# SCH_AP-DIsplay-2_1_Altium.net
KiCad netlist of a schematic drawn in Altium Designer
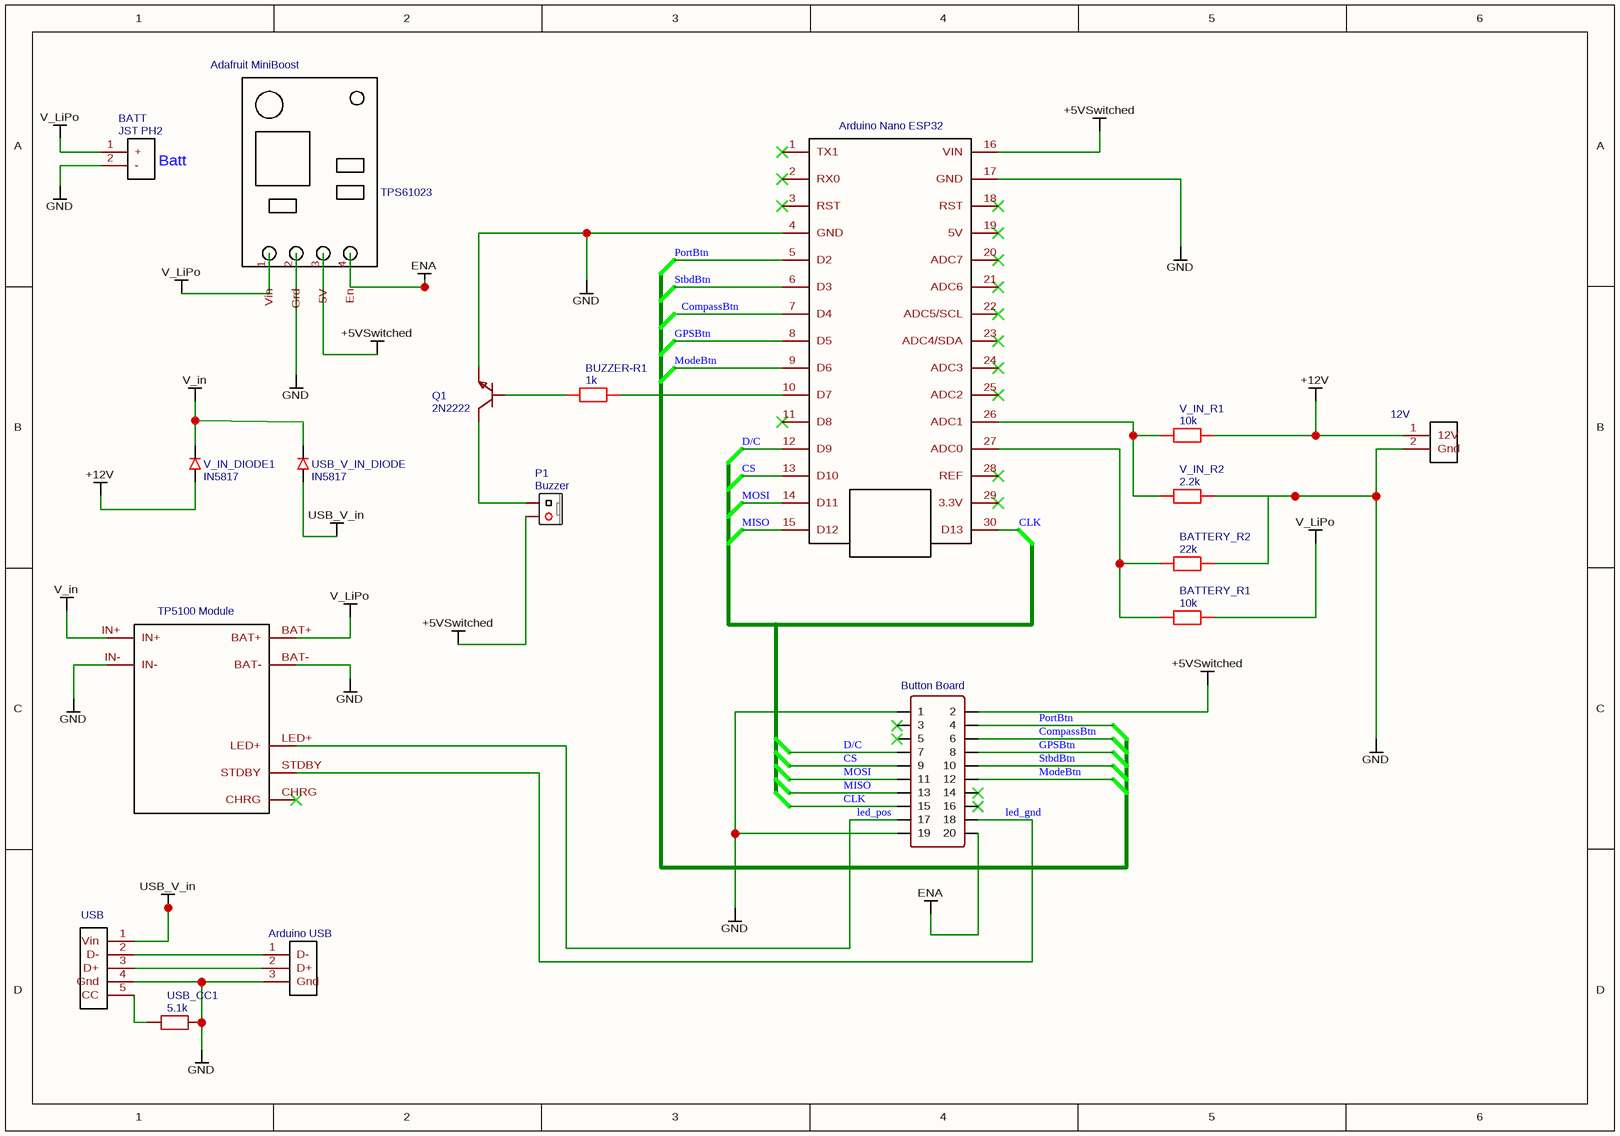
[diagram p0: SCH_AP-DIsplay-2.1_Altium.schdoc]

(export (version "E")
  (design (tool "Eeschema 10.0.6"))
  (components
    (comp (ref "1X2_JST_XH")
      (value "12V")
      (fields (field (name "CONTRIBUTOR") "edelarosar1700"))
      (libsource (lib "altium-import") (part "root_2_12V_"))
    )
    (comp (ref "BATT")
      (value "JST PH2")
      (fields (field (name "CONTRIBUTOR") "pwarrow99"))
      (libsource (lib "altium-import") (part "root_0_JST PH2_"))
    )
    (comp (ref "BATTERY_R1")
      (value "10k")
      (fields (field (name "CONTRIBUTOR") "Kagutsuchi"))
      (libsource (lib "altium-import") (part "root_0_10k_"))
    )
    (comp (ref "BATTERY_R2")
      (value "22k")
      (fields (field (name "CONTRIBUTOR") "Kagutsuchi"))
      (libsource (lib "altium-import") (part "root_0_22k_"))
    )
    (comp (ref "BUTTON_LED1")
      (value "Button Board")
      (fields (field (name "CONTRIBUTOR") "LCEDA_Lib"))
      (libsource (lib "altium-import") (part "root_0_Button Board_"))
    )
    (comp (ref "BUZZER-R1")
      (value "1k")
      (fields (field (name "CONTRIBUTOR") "Kagutsuchi"))
      (libsource (lib "altium-import") (part "root_0_1k_"))
    )
    (comp (ref "JST_XH_1X3")
      (value "Arduino USB")
      (fields (field (name "CONTRIBUTOR") "GeMeMe"))
      (libsource (lib "altium-import") (part "root_0_Arduino USB_"))
    )
    (comp (ref "JST_XH_1X5")
      (value "USB")
      (fields (field (name "CONTRIBUTOR") "GeMeMe"))
      (libsource (lib "altium-import") (part "root_0_USB_"))
    )
    (comp (ref "P1")
      (value "Buzzer")
      (fields
        (field (name "MANUFACTURER PART") "Headers  Pins2.54mm1*10P")
        (field (name "CONTRIBUTOR") "jousterde1")
      )
      (libsource (lib "altium-import") (part "root_0_Buzzer_"))
    )
    (comp (ref "Q1")
      (value "2N2222")
      (fields
        (field (name "MANUFACTURER") "ST(先科)")
        (field (name "MANUFACTURER PART") "2N2222A")
        (field (name "CONTRIBUTOR") "LCSC")
      )
      (libsource (lib "altium-import") (part "root_2_2N2222_"))
    )
    (comp (ref "TPS61023")
      (value "Adafruit MiniBoost")
      (fields (field (name "CONTRIBUTOR") "jefflorditch"))
      (libsource (lib "altium-import") (part "root_0_Adafruit MiniBoost_"))
    )
    (comp (ref "U1")
      (value "Arduino Nano ESP32")
      (fields (field (name "CONTRIBUTOR") "Nikolay Yanev"))
      (libsource (lib "altium-import") (part "root_0_Arduino Nano ESP32_"))
    )
    (comp (ref "U3")
      (value "TP5100 Module")
      (fields (field (name "MANUFACTURER PART") "TP5100-MODULE") (field (name "CONTRIBUTOR") "cropemail"))
      (libsource (lib "altium-import") (part "root_0_TP5100 Module_"))
    )
    (comp (ref "USB_CC1")
      (value "5.1k")
      (fields (field (name "CONTRIBUTOR") "LCEDA_Lib"))
      (libsource (lib "altium-import") (part "root_2_5.1k_"))
    )
    (comp (ref "USB_V_IN_DIODE")
      (value "IN5817")
      (fields (field (name "MANUFACTURER PART") "DIODE") (field (name "CONTRIBUTOR") "mimit.oscar"))
      (libsource (lib "altium-import") (part "root_1_IN5817_"))
    )
    (comp (ref "V_IN_DIODE1")
      (value "IN5817")
      (fields (field (name "MANUFACTURER PART") "DIODE") (field (name "CONTRIBUTOR") "mimit.oscar"))
      (libsource (lib "altium-import") (part "root_1_IN5817_"))
    )
    (comp (ref "V_IN_R1")
      (value "10k")
      (fields (field (name "CONTRIBUTOR") "Kagutsuchi"))
      (libsource (lib "altium-import") (part "root_0_10k_"))
    )
    (comp (ref "V_IN_R2")
      (value "2.2k")
      (fields (field (name "CONTRIBUTOR") "Kagutsuchi"))
      (libsource (lib "altium-import") (part "root_0_2.2k_"))
    )
  )
  (nets
    (net (code "1") (name "+5VSwitched") (class "Default")
      (node (ref "BUTTON_LED1") (pin "2") (pinfunction "2_2") (pintype "passive"))
      (node (ref "P1") (pin "2") (pinfunction "2_2") (pintype "passive"))
      (node (ref "TPS61023") (pin "3") (pinfunction "5V_3") (pintype "passive"))
      (node (ref "U1") (pin "16") (pinfunction "VIN_16") (pintype "passive"))
    )
    (net (code "2") (name "+12V") (class "Default")
      (node (ref "1X2_JST_XH") (pin "1") (pinfunction "12V_1") (pintype "passive"))
      (node (ref "V_IN_DIODE1") (pin "1") (pinfunction "1_1") (pintype "passive"))
      (node (ref "V_IN_R1") (pin "2") (pinfunction "1_2") (pintype "passive"))
    )
    (net (code "3") (name "/CLK") (class "Default")
      (node (ref "BUTTON_LED1") (pin "15") (pinfunction "15_15") (pintype "passive"))
      (node (ref "U1") (pin "30") (pinfunction "D13_30") (pintype "passive"))
    )
    (net (code "4") (name "/CS") (class "Default")
      (node (ref "BUTTON_LED1") (pin "9") (pinfunction "9_9") (pintype "passive"))
      (node (ref "U1") (pin "13") (pinfunction "D10_13") (pintype "passive"))
    )
    (net (code "5") (name "/CompassBtn") (class "Default")
      (node (ref "BUTTON_LED1") (pin "6") (pinfunction "6_6") (pintype "passive"))
      (node (ref "U1") (pin "7") (pinfunction "D4_7") (pintype "passive"))
    )
    (net (code "6") (name "/D{slash}C") (class "Default")
      (node (ref "BUTTON_LED1") (pin "7") (pinfunction "7_7") (pintype "passive"))
      (node (ref "U1") (pin "12") (pinfunction "D9_12") (pintype "passive"))
    )
    (net (code "7") (name "/GPSBtn") (class "Default")
      (node (ref "BUTTON_LED1") (pin "8") (pinfunction "8_8") (pintype "passive"))
      (node (ref "U1") (pin "8") (pinfunction "D5_8") (pintype "passive"))
    )
    (net (code "8") (name "/MISO") (class "Default")
      (node (ref "BUTTON_LED1") (pin "13") (pinfunction "13_13") (pintype "passive"))
      (node (ref "U1") (pin "15") (pinfunction "D12_15") (pintype "passive"))
    )
    (net (code "9") (name "/MOSI") (class "Default")
      (node (ref "BUTTON_LED1") (pin "11") (pinfunction "11_11") (pintype "passive"))
      (node (ref "U1") (pin "14") (pinfunction "D11_14") (pintype "passive"))
    )
    (net (code "10") (name "/ModeBtn") (class "Default")
      (node (ref "BUTTON_LED1") (pin "12") (pinfunction "12_12") (pintype "passive"))
      (node (ref "U1") (pin "9") (pinfunction "D6_9") (pintype "passive"))
    )
    (net (code "11") (name "/PortBtn") (class "Default")
      (node (ref "BUTTON_LED1") (pin "4") (pinfunction "4_4") (pintype "passive"))
      (node (ref "U1") (pin "5") (pinfunction "D2_5") (pintype "passive"))
    )
    (net (code "12") (name "/StbdBtn") (class "Default")
      (node (ref "BUTTON_LED1") (pin "10") (pinfunction "10_10") (pintype "passive"))
      (node (ref "U1") (pin "6") (pinfunction "D3_6") (pintype "passive"))
    )
    (net (code "13") (name "/led_gnd") (class "Default")
      (node (ref "BUTTON_LED1") (pin "18") (pinfunction "18_18") (pintype "passive"))
      (node (ref "U3") (pin "STDBY") (pinfunction "STDBY_STDBY") (pintype "passive"))
    )
    (net (code "14") (name "/led_pos") (class "Default")
      (node (ref "BUTTON_LED1") (pin "17") (pinfunction "17_17") (pintype "passive"))
      (node (ref "U3") (pin "LED+") (pinfunction "LED+_LED+") (pintype "passive"))
    )
    (net (code "15") (name "ENA") (class "Default")
      (node (ref "BUTTON_LED1") (pin "20") (pinfunction "20_20") (pintype "passive"))
      (node (ref "TPS61023") (pin "4") (pinfunction "En_4") (pintype "passive"))
    )
    (net (code "16") (name "GND") (class "Default")
      (node (ref "1X2_JST_XH") (pin "2") (pinfunction "Gnd_2") (pintype "passive"))
      (node (ref "BATT") (pin "2") (pinfunction "-_2") (pintype "passive"))
      (node (ref "BATTERY_R2") (pin "2") (pinfunction "1_2") (pintype "passive"))
      (node (ref "BUTTON_LED1") (pin "1") (pinfunction "1_1") (pintype "passive"))
      (node (ref "BUTTON_LED1") (pin "19") (pinfunction "19_19") (pintype "passive"))
      (node (ref "JST_XH_1X3") (pin "3") (pinfunction "Gnd_3") (pintype "passive"))
      (node (ref "JST_XH_1X5") (pin "4") (pinfunction "Gnd_4") (pintype "passive"))
      (node (ref "Q1") (pin "1") (pinfunction "E_1") (pintype "passive"))
      (node (ref "TPS61023") (pin "2") (pinfunction "Grd_2") (pintype "passive"))
      (node (ref "U1") (pin "17") (pinfunction "GND_17") (pintype "passive"))
      (node (ref "U1") (pin "4") (pinfunction "GND_4") (pintype "passive"))
      (node (ref "U3") (pin "BAT-") (pinfunction "BAT-_BAT-") (pintype "passive"))
      (node (ref "U3") (pin "IN-") (pinfunction "IN-_IN-") (pintype "passive"))
      (node (ref "USB_CC1") (pin "1") (pinfunction "1_1") (pintype "passive"))
      (node (ref "V_IN_R2") (pin "2") (pinfunction "1_2") (pintype "passive"))
    )
    (net (code "17") (name "Net-(BATTERY_R1-2)") (class "Default")
      (node (ref "BATTERY_R1") (pin "1") (pinfunction "2_1") (pintype "passive"))
      (node (ref "BATTERY_R2") (pin "1") (pinfunction "2_1") (pintype "passive"))
      (node (ref "U1") (pin "27") (pinfunction "ADC0_27") (pintype "passive"))
    )
    (net (code "18") (name "Net-(BUZZER-R1-1)") (class "Default")
      (node (ref "BUZZER-R1") (pin "2") (pinfunction "1_2") (pintype "passive"))
      (node (ref "U1") (pin "10") (pinfunction "D7_10") (pintype "passive"))
    )
    (net (code "19") (name "Net-(BUZZER-R1-2)") (class "Default")
      (node (ref "BUZZER-R1") (pin "1") (pinfunction "2_1") (pintype "passive"))
      (node (ref "Q1") (pin "2") (pinfunction "B_2") (pintype "passive"))
    )
    (net (code "20") (name "Net-(JST_XH_1X3-D+)") (class "Default")
      (node (ref "JST_XH_1X3") (pin "2") (pinfunction "D+_2") (pintype "passive"))
      (node (ref "JST_XH_1X5") (pin "3") (pinfunction "D+_3") (pintype "passive"))
    )
    (net (code "21") (name "Net-(JST_XH_1X3-D-)") (class "Default")
      (node (ref "JST_XH_1X3") (pin "1") (pinfunction "D-_1") (pintype "passive"))
      (node (ref "JST_XH_1X5") (pin "2") (pinfunction "D-_2") (pintype "passive"))
    )
    (net (code "22") (name "Net-(JST_XH_1X5-CC)") (class "Default")
      (node (ref "JST_XH_1X5") (pin "5") (pinfunction "CC_5") (pintype "passive"))
      (node (ref "USB_CC1") (pin "2") (pinfunction "2_2") (pintype "passive"))
    )
    (net (code "23") (name "Net-(Q1-C)") (class "Default")
      (node (ref "P1") (pin "1") (pinfunction "1_1") (pintype "passive"))
      (node (ref "Q1") (pin "3") (pinfunction "C_3") (pintype "passive"))
    )
    (net (code "24") (name "Net-(U1-ADC1)") (class "Default")
      (node (ref "U1") (pin "26") (pinfunction "ADC1_26") (pintype "passive"))
      (node (ref "V_IN_R1") (pin "1") (pinfunction "2_1") (pintype "passive"))
      (node (ref "V_IN_R2") (pin "1") (pinfunction "2_1") (pintype "passive"))
    )
    (net (code "25") (name "USB_V_in") (class "Default")
      (node (ref "JST_XH_1X5") (pin "1") (pinfunction "Vin_1") (pintype "passive"))
      (node (ref "USB_V_IN_DIODE") (pin "1") (pinfunction "1_1") (pintype "passive"))
    )
    (net (code "26") (name "V_LiPo") (class "Default")
      (node (ref "BATT") (pin "1") (pinfunction "+_1") (pintype "passive"))
      (node (ref "BATTERY_R1") (pin "2") (pinfunction "1_2") (pintype "passive"))
      (node (ref "TPS61023") (pin "1") (pinfunction "Vin_1") (pintype "passive"))
      (node (ref "U3") (pin "BAT+") (pinfunction "BAT+_BAT+") (pintype "passive"))
    )
    (net (code "27") (name "V_in") (class "Default")
      (node (ref "U3") (pin "IN+") (pinfunction "IN+_IN+") (pintype "passive"))
      (node (ref "USB_V_IN_DIODE") (pin "2") (pinfunction "2_2") (pintype "passive"))
      (node (ref "V_IN_DIODE1") (pin "2") (pinfunction "2_2") (pintype "passive"))
    )
    (net (code "28") (name "unconnected-(BUTTON_LED1-Pad3)") (class "Default")
      (node (ref "BUTTON_LED1") (pin "3") (pinfunction "3_3") (pintype "passive+no_connect"))
    )
    (net (code "29") (name "unconnected-(BUTTON_LED1-Pad5)") (class "Default")
      (node (ref "BUTTON_LED1") (pin "5") (pinfunction "5_5") (pintype "passive+no_connect"))
    )
    (net (code "30") (name "unconnected-(BUTTON_LED1-Pad14)") (class "Default")
      (node (ref "BUTTON_LED1") (pin "14") (pinfunction "14_14") (pintype "passive+no_connect"))
    )
    (net (code "31") (name "unconnected-(BUTTON_LED1-Pad16)") (class "Default")
      (node (ref "BUTTON_LED1") (pin "16") (pinfunction "16_16") (pintype "passive+no_connect"))
    )
    (net (code "32") (name "unconnected-(U1-3.3V-Pad29)") (class "Default")
      (node (ref "U1") (pin "29") (pinfunction "3.3V_29") (pintype "passive+no_connect"))
    )
    (net (code "33") (name "unconnected-(U1-5V-Pad19)") (class "Default")
      (node (ref "U1") (pin "19") (pinfunction "5V_19") (pintype "passive+no_connect"))
    )
    (net (code "34") (name "unconnected-(U1-ADC2-Pad25)") (class "Default")
      (node (ref "U1") (pin "25") (pinfunction "ADC2_25") (pintype "passive+no_connect"))
    )
    (net (code "35") (name "unconnected-(U1-ADC3-Pad24)") (class "Default")
      (node (ref "U1") (pin "24") (pinfunction "ADC3_24") (pintype "passive+no_connect"))
    )
    (net (code "36") (name "unconnected-(U1-ADC4{slash}SDA-Pad23)") (class "Default")
      (node (ref "U1") (pin "23") (pinfunction "ADC4/SDA_23") (pintype "passive+no_connect"))
    )
    (net (code "37") (name "unconnected-(U1-ADC5{slash}SCL-Pad22)") (class "Default")
      (node (ref "U1") (pin "22") (pinfunction "ADC5/SCL_22") (pintype "passive+no_connect"))
    )
    (net (code "38") (name "unconnected-(U1-ADC6-Pad21)") (class "Default")
      (node (ref "U1") (pin "21") (pinfunction "ADC6_21") (pintype "passive+no_connect"))
    )
    (net (code "39") (name "unconnected-(U1-ADC7-Pad20)") (class "Default")
      (node (ref "U1") (pin "20") (pinfunction "ADC7_20") (pintype "passive+no_connect"))
    )
    (net (code "40") (name "unconnected-(U1-D8-Pad11)") (class "Default")
      (node (ref "U1") (pin "11") (pinfunction "D8_11") (pintype "passive+no_connect"))
    )
    (net (code "41") (name "unconnected-(U1-REF-Pad28)") (class "Default")
      (node (ref "U1") (pin "28") (pinfunction "REF_28") (pintype "passive+no_connect"))
    )
    (net (code "42") (name "unconnected-(U1-RST-Pad3)") (class "Default")
      (node (ref "U1") (pin "3") (pinfunction "RST_3") (pintype "passive+no_connect"))
    )
    (net (code "43") (name "unconnected-(U1-RST-Pad18)") (class "Default")
      (node (ref "U1") (pin "18") (pinfunction "RST_18") (pintype "passive+no_connect"))
    )
    (net (code "44") (name "unconnected-(U1-RX0-Pad2)") (class "Default")
      (node (ref "U1") (pin "2") (pinfunction "RX0_2") (pintype "passive+no_connect"))
    )
    (net (code "45") (name "unconnected-(U1-TX1-Pad1)") (class "Default")
      (node (ref "U1") (pin "1") (pinfunction "TX1_1") (pintype "passive+no_connect"))
    )
    (net (code "46") (name "unconnected-(U3-PadCHRG)") (class "Default")
      (node (ref "U3") (pin "CHRG") (pinfunction "CHRG_CHRG") (pintype "passive+no_connect"))
    )
  )
)
